# driver_2.net
KiCad netlist of a schematic drawn in EAGLE
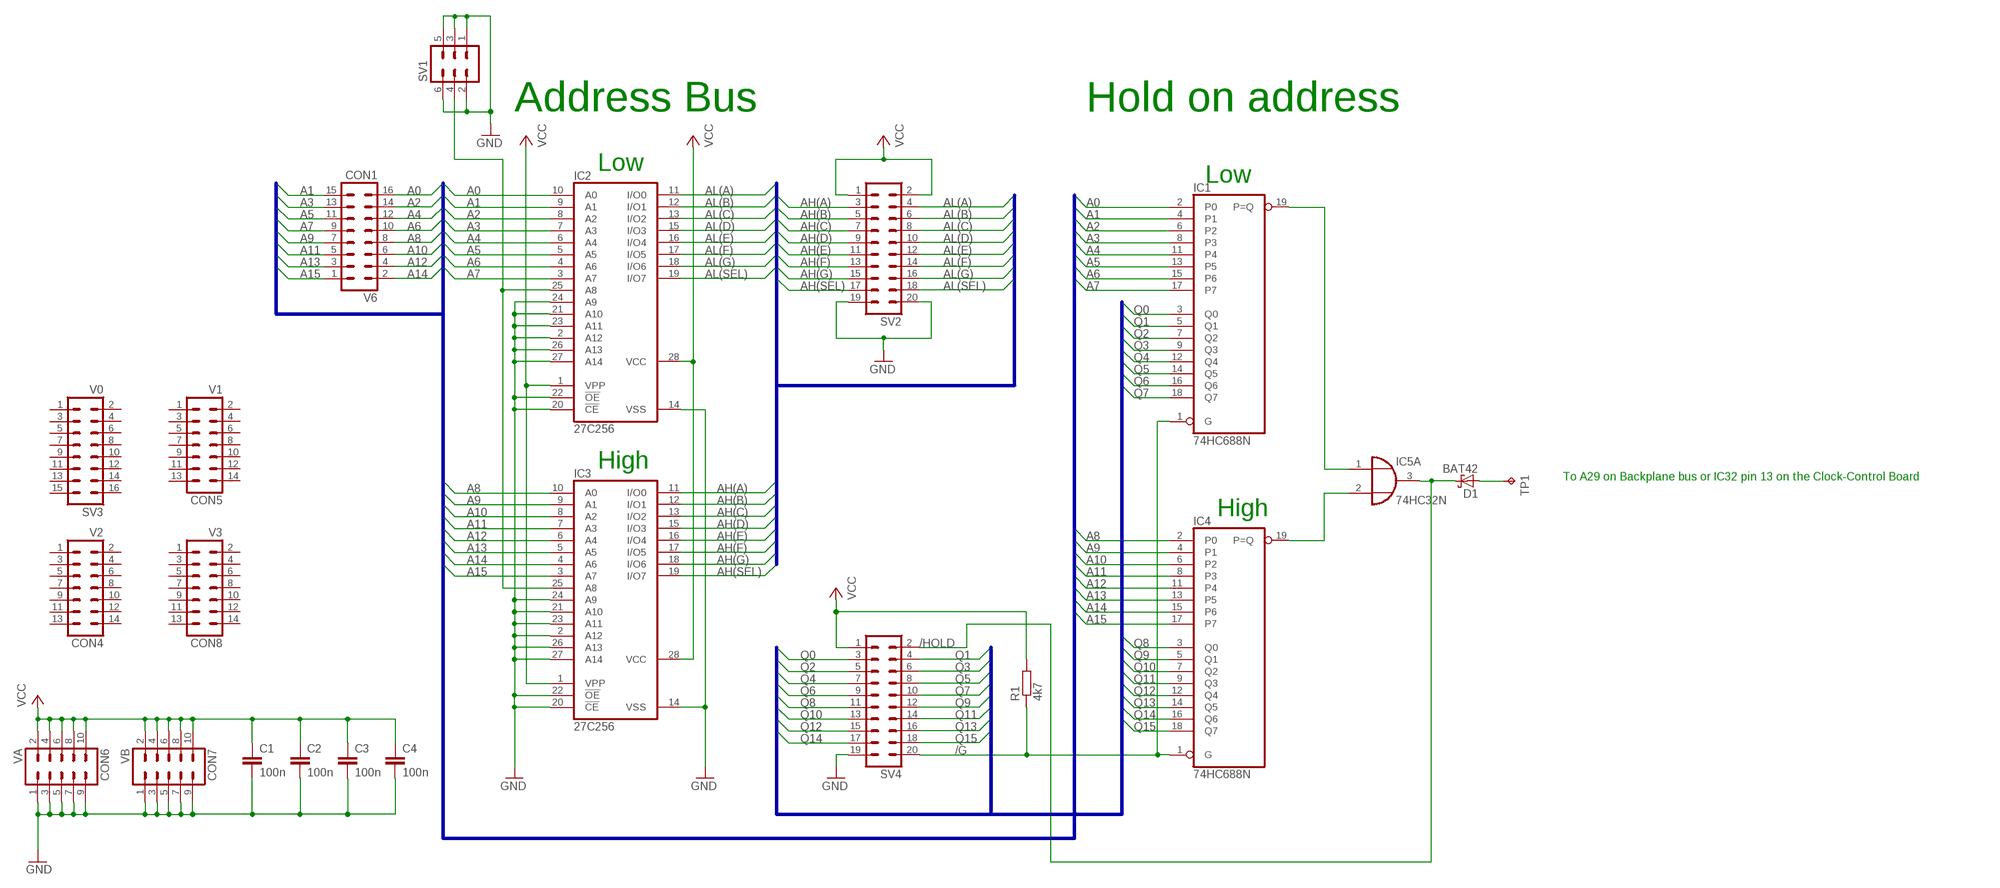
[diagram p0: schematic, sheet 1]

(export (version "E")
  (design (tool "Eeschema 10.0.6"))
  (components
    (comp (ref "C1")
      (value "100n")
      (footprint "eagle-import:C050-024X044")
      (libsource (lib "eagle-import") (part "C-EU050-024X044"))
    )
    (comp (ref "C2")
      (value "100n")
      (footprint "eagle-import:C050-024X044")
      (libsource (lib "eagle-import") (part "C-EU050-024X044"))
    )
    (comp (ref "C3")
      (value "100n")
      (footprint "eagle-import:C050-024X044")
      (libsource (lib "eagle-import") (part "C-EU050-024X044"))
    )
    (comp (ref "C4")
      (value "100n")
      (footprint "eagle-import:C050-024X044")
      (libsource (lib "eagle-import") (part "C-EU050-024X044"))
    )
    (comp (ref "CON1")
      (value "V6")
      (footprint "eagle-import:ML16")
      (libsource (lib "eagle-import") (part "ML16"))
    )
    (comp (ref "CON4")
      (value "V2")
      (footprint "eagle-import:ML14")
      (libsource (lib "eagle-import") (part "ML14"))
    )
    (comp (ref "CON5")
      (value "V1")
      (footprint "eagle-import:ML14")
      (fields (field (name "OC_FARNELL") "unknown") (field (name "OC_NEWARK") "unknown"))
      (libsource (lib "eagle-import") (part "ML14"))
    )
    (comp (ref "CON6")
      (value "VA")
      (footprint "eagle-import:ML10")
      (libsource (lib "eagle-import") (part "ML10"))
    )
    (comp (ref "CON7")
      (value "VB")
      (footprint "eagle-import:ML10")
      (libsource (lib "eagle-import") (part "ML10"))
    )
    (comp (ref "CON8")
      (value "V3")
      (footprint "eagle-import:ML14")
      (libsource (lib "eagle-import") (part "ML14"))
    )
    (comp (ref "D1")
      (value "BAT42")
      (footprint "eagle-import:DO35-10")
      (libsource (lib "eagle-import") (part "BAT42"))
    )
    (comp (ref "IC1")
      (value "74HC688N")
      (footprint "eagle-import:DIL20")
      (libsource (lib "eagle-import") (part "74688NHC"))
    )
    (comp (ref "IC2")
      (value "27C256")
      (footprint "eagle-import:DIL28-6")
      (libsource (lib "eagle-import") (part "27C256AG"))
    )
    (comp (ref "IC3")
      (value "27C256")
      (footprint "eagle-import:DIL28-6")
      (libsource (lib "eagle-import") (part "27C256AG"))
    )
    (comp (ref "IC4")
      (value "74HC688N")
      (footprint "eagle-import:DIL20")
      (libsource (lib "eagle-import") (part "74688NHC"))
    )
    (comp (ref "IC5")
      (value "74HC32N")
      (footprint "eagle-import:DIL14")
      (libsource (lib "eagle-import") (part "7432NHC"))
    )
    (comp (ref "R1")
      (value "4k7")
      (footprint "eagle-import:0204_5")
      (libsource (lib "eagle-import") (part "R-EU_0204/5"))
    )
    (comp (ref "SV1")
      (value "ML6")
      (footprint "eagle-import:ML6")
      (libsource (lib "eagle-import") (part "ML6"))
    )
    (comp (ref "SV2")
      (value "ML20L")
      (footprint "eagle-import:ML20L")
      (libsource (lib "eagle-import") (part "ML20L"))
    )
    (comp (ref "SV3")
      (value "V0")
      (footprint "eagle-import:ML16")
      (libsource (lib "eagle-import") (part "ML16"))
    )
    (comp (ref "SV4")
      (value "ML20L")
      (footprint "eagle-import:ML20L")
      (libsource (lib "eagle-import") (part "ML20L"))
    )
    (comp (ref "TP1")
      (value "Interface -> R12")
      (footprint "eagle-import:P1-17")
      (libsource (lib "eagle-import") (part "TPPAD1-17"))
    )
  )
  (nets
    (net (code "1") (name "/A0") (class "Default")
      (node (ref "CON1") (pin "16") (pinfunction "16_16") (pintype "passive"))
      (node (ref "IC1") (pin "2") (pinfunction "P0_2") (pintype "input"))
      (node (ref "IC2") (pin "10") (pinfunction "A0_10") (pintype "input"))
    )
    (net (code "2") (name "/A1") (class "Default")
      (node (ref "CON1") (pin "15") (pinfunction "15_15") (pintype "passive"))
      (node (ref "IC1") (pin "4") (pinfunction "P1_4") (pintype "input"))
      (node (ref "IC2") (pin "9") (pinfunction "A1_9") (pintype "input"))
    )
    (net (code "3") (name "/A2") (class "Default")
      (node (ref "CON1") (pin "14") (pinfunction "14_14") (pintype "passive"))
      (node (ref "IC1") (pin "6") (pinfunction "P2_6") (pintype "input"))
      (node (ref "IC2") (pin "8") (pinfunction "A2_8") (pintype "input"))
    )
    (net (code "4") (name "/A3") (class "Default")
      (node (ref "CON1") (pin "13") (pinfunction "13_13") (pintype "passive"))
      (node (ref "IC1") (pin "8") (pinfunction "P3_8") (pintype "input"))
      (node (ref "IC2") (pin "7") (pinfunction "A3_7") (pintype "input"))
    )
    (net (code "5") (name "/A4") (class "Default")
      (node (ref "CON1") (pin "12") (pinfunction "12_12") (pintype "passive"))
      (node (ref "IC1") (pin "11") (pinfunction "P4_11") (pintype "input"))
      (node (ref "IC2") (pin "6") (pinfunction "A4_6") (pintype "input"))
    )
    (net (code "6") (name "/A5") (class "Default")
      (node (ref "CON1") (pin "11") (pinfunction "11_11") (pintype "passive"))
      (node (ref "IC1") (pin "13") (pinfunction "P5_13") (pintype "input"))
      (node (ref "IC2") (pin "5") (pinfunction "A5_5") (pintype "input"))
    )
    (net (code "7") (name "/A6") (class "Default")
      (node (ref "CON1") (pin "10") (pinfunction "10_10") (pintype "passive"))
      (node (ref "IC1") (pin "15") (pinfunction "P6_15") (pintype "input"))
      (node (ref "IC2") (pin "4") (pinfunction "A6_4") (pintype "input"))
    )
    (net (code "8") (name "/A7") (class "Default")
      (node (ref "CON1") (pin "9") (pinfunction "9_9") (pintype "passive"))
      (node (ref "IC1") (pin "17") (pinfunction "P7_17") (pintype "input"))
      (node (ref "IC2") (pin "3") (pinfunction "A7_3") (pintype "input"))
    )
    (net (code "9") (name "/A8") (class "Default")
      (node (ref "CON1") (pin "8") (pinfunction "8_8") (pintype "passive"))
      (node (ref "IC3") (pin "10") (pinfunction "A0_10") (pintype "input"))
      (node (ref "IC4") (pin "2") (pinfunction "P0_2") (pintype "input"))
    )
    (net (code "10") (name "/A9") (class "Default")
      (node (ref "CON1") (pin "7") (pinfunction "7_7") (pintype "passive"))
      (node (ref "IC3") (pin "9") (pinfunction "A1_9") (pintype "input"))
      (node (ref "IC4") (pin "4") (pinfunction "P1_4") (pintype "input"))
    )
    (net (code "11") (name "/A10") (class "Default")
      (node (ref "CON1") (pin "6") (pinfunction "6_6") (pintype "passive"))
      (node (ref "IC3") (pin "8") (pinfunction "A2_8") (pintype "input"))
      (node (ref "IC4") (pin "6") (pinfunction "P2_6") (pintype "input"))
    )
    (net (code "12") (name "/A11") (class "Default")
      (node (ref "CON1") (pin "5") (pinfunction "5_5") (pintype "passive"))
      (node (ref "IC3") (pin "7") (pinfunction "A3_7") (pintype "input"))
      (node (ref "IC4") (pin "8") (pinfunction "P3_8") (pintype "input"))
    )
    (net (code "13") (name "/A12") (class "Default")
      (node (ref "CON1") (pin "4") (pinfunction "4_4") (pintype "passive"))
      (node (ref "IC3") (pin "6") (pinfunction "A4_6") (pintype "input"))
      (node (ref "IC4") (pin "11") (pinfunction "P4_11") (pintype "input"))
    )
    (net (code "14") (name "/A13") (class "Default")
      (node (ref "CON1") (pin "3") (pinfunction "3_3") (pintype "passive"))
      (node (ref "IC3") (pin "5") (pinfunction "A5_5") (pintype "input"))
      (node (ref "IC4") (pin "13") (pinfunction "P5_13") (pintype "input"))
    )
    (net (code "15") (name "/A14") (class "Default")
      (node (ref "CON1") (pin "2") (pinfunction "2_2") (pintype "passive"))
      (node (ref "IC3") (pin "4") (pinfunction "A6_4") (pintype "input"))
      (node (ref "IC4") (pin "15") (pinfunction "P6_15") (pintype "input"))
    )
    (net (code "16") (name "/A15") (class "Default")
      (node (ref "CON1") (pin "1") (pinfunction "1_1") (pintype "passive"))
      (node (ref "IC3") (pin "3") (pinfunction "A7_3") (pintype "input"))
      (node (ref "IC4") (pin "17") (pinfunction "P7_17") (pintype "input"))
    )
    (net (code "17") (name "/AH(A)") (class "Default")
      (node (ref "IC3") (pin "11") (pinfunction "I/O0_11") (pintype "tri_state"))
      (node (ref "SV2") (pin "3") (pinfunction "3_3") (pintype "passive"))
    )
    (net (code "18") (name "/AH(B)") (class "Default")
      (node (ref "IC3") (pin "12") (pinfunction "I/O1_12") (pintype "tri_state"))
      (node (ref "SV2") (pin "5") (pinfunction "5_5") (pintype "passive"))
    )
    (net (code "19") (name "/AH(C)") (class "Default")
      (node (ref "IC3") (pin "13") (pinfunction "I/O2_13") (pintype "tri_state"))
      (node (ref "SV2") (pin "7") (pinfunction "7_7") (pintype "passive"))
    )
    (net (code "20") (name "/AH(D)") (class "Default")
      (node (ref "IC3") (pin "15") (pinfunction "I/O3_15") (pintype "tri_state"))
      (node (ref "SV2") (pin "9") (pinfunction "9_9") (pintype "passive"))
    )
    (net (code "21") (name "/AH(E)") (class "Default")
      (node (ref "IC3") (pin "16") (pinfunction "I/O4_16") (pintype "tri_state"))
      (node (ref "SV2") (pin "11") (pinfunction "11_11") (pintype "passive"))
    )
    (net (code "22") (name "/AH(F)") (class "Default")
      (node (ref "IC3") (pin "17") (pinfunction "I/O5_17") (pintype "tri_state"))
      (node (ref "SV2") (pin "13") (pinfunction "13_13") (pintype "passive"))
    )
    (net (code "23") (name "/AH(G)") (class "Default")
      (node (ref "IC3") (pin "18") (pinfunction "I/O6_18") (pintype "tri_state"))
      (node (ref "SV2") (pin "15") (pinfunction "15_15") (pintype "passive"))
    )
    (net (code "24") (name "/AH(SEL)") (class "Default")
      (node (ref "IC3") (pin "19") (pinfunction "I/O7_19") (pintype "tri_state"))
      (node (ref "SV2") (pin "17") (pinfunction "17_17") (pintype "passive"))
    )
    (net (code "25") (name "/AL(A)") (class "Default")
      (node (ref "IC2") (pin "11") (pinfunction "I/O0_11") (pintype "tri_state"))
      (node (ref "SV2") (pin "4") (pinfunction "4_4") (pintype "passive"))
    )
    (net (code "26") (name "/AL(B)") (class "Default")
      (node (ref "IC2") (pin "12") (pinfunction "I/O1_12") (pintype "tri_state"))
      (node (ref "SV2") (pin "6") (pinfunction "6_6") (pintype "passive"))
    )
    (net (code "27") (name "/AL(C)") (class "Default")
      (node (ref "IC2") (pin "13") (pinfunction "I/O2_13") (pintype "tri_state"))
      (node (ref "SV2") (pin "8") (pinfunction "8_8") (pintype "passive"))
    )
    (net (code "28") (name "/AL(D)") (class "Default")
      (node (ref "IC2") (pin "15") (pinfunction "I/O3_15") (pintype "tri_state"))
      (node (ref "SV2") (pin "10") (pinfunction "10_10") (pintype "passive"))
    )
    (net (code "29") (name "/AL(E)") (class "Default")
      (node (ref "IC2") (pin "16") (pinfunction "I/O4_16") (pintype "tri_state"))
      (node (ref "SV2") (pin "12") (pinfunction "12_12") (pintype "passive"))
    )
    (net (code "30") (name "/AL(F)") (class "Default")
      (node (ref "IC2") (pin "17") (pinfunction "I/O5_17") (pintype "tri_state"))
      (node (ref "SV2") (pin "14") (pinfunction "14_14") (pintype "passive"))
    )
    (net (code "31") (name "/AL(G)") (class "Default")
      (node (ref "IC2") (pin "18") (pinfunction "I/O6_18") (pintype "tri_state"))
      (node (ref "SV2") (pin "16") (pinfunction "16_16") (pintype "passive"))
    )
    (net (code "32") (name "/AL(SEL)") (class "Default")
      (node (ref "IC2") (pin "19") (pinfunction "I/O7_19") (pintype "tri_state"))
      (node (ref "SV2") (pin "18") (pinfunction "18_18") (pintype "passive"))
    )
    (net (code "33") (name "/Q0") (class "Default")
      (node (ref "IC1") (pin "3") (pinfunction "Q0_3") (pintype "input"))
      (node (ref "SV4") (pin "3") (pinfunction "3_3") (pintype "passive"))
    )
    (net (code "34") (name "/Q1") (class "Default")
      (node (ref "IC1") (pin "5") (pinfunction "Q1_5") (pintype "input"))
      (node (ref "SV4") (pin "4") (pinfunction "4_4") (pintype "passive"))
    )
    (net (code "35") (name "/Q2") (class "Default")
      (node (ref "IC1") (pin "7") (pinfunction "Q2_7") (pintype "input"))
      (node (ref "SV4") (pin "5") (pinfunction "5_5") (pintype "passive"))
    )
    (net (code "36") (name "/Q3") (class "Default")
      (node (ref "IC1") (pin "9") (pinfunction "Q3_9") (pintype "input"))
      (node (ref "SV4") (pin "6") (pinfunction "6_6") (pintype "passive"))
    )
    (net (code "37") (name "/Q4") (class "Default")
      (node (ref "IC1") (pin "12") (pinfunction "Q4_12") (pintype "input"))
      (node (ref "SV4") (pin "7") (pinfunction "7_7") (pintype "passive"))
    )
    (net (code "38") (name "/Q5") (class "Default")
      (node (ref "IC1") (pin "14") (pinfunction "Q5_14") (pintype "input"))
      (node (ref "SV4") (pin "8") (pinfunction "8_8") (pintype "passive"))
    )
    (net (code "39") (name "/Q6") (class "Default")
      (node (ref "IC1") (pin "16") (pinfunction "Q6_16") (pintype "input"))
      (node (ref "SV4") (pin "9") (pinfunction "9_9") (pintype "passive"))
    )
    (net (code "40") (name "/Q7") (class "Default")
      (node (ref "IC1") (pin "18") (pinfunction "Q7_18") (pintype "input"))
      (node (ref "SV4") (pin "10") (pinfunction "10_10") (pintype "passive"))
    )
    (net (code "41") (name "/Q8") (class "Default")
      (node (ref "IC4") (pin "3") (pinfunction "Q0_3") (pintype "input"))
      (node (ref "SV4") (pin "11") (pinfunction "11_11") (pintype "passive"))
    )
    (net (code "42") (name "/Q9") (class "Default")
      (node (ref "IC4") (pin "5") (pinfunction "Q1_5") (pintype "input"))
      (node (ref "SV4") (pin "12") (pinfunction "12_12") (pintype "passive"))
    )
    (net (code "43") (name "/Q10") (class "Default")
      (node (ref "IC4") (pin "7") (pinfunction "Q2_7") (pintype "input"))
      (node (ref "SV4") (pin "13") (pinfunction "13_13") (pintype "passive"))
    )
    (net (code "44") (name "/Q11") (class "Default")
      (node (ref "IC4") (pin "9") (pinfunction "Q3_9") (pintype "input"))
      (node (ref "SV4") (pin "14") (pinfunction "14_14") (pintype "passive"))
    )
    (net (code "45") (name "/Q12") (class "Default")
      (node (ref "IC4") (pin "12") (pinfunction "Q4_12") (pintype "input"))
      (node (ref "SV4") (pin "15") (pinfunction "15_15") (pintype "passive"))
    )
    (net (code "46") (name "/Q13") (class "Default")
      (node (ref "IC4") (pin "14") (pinfunction "Q5_14") (pintype "input"))
      (node (ref "SV4") (pin "16") (pinfunction "16_16") (pintype "passive"))
    )
    (net (code "47") (name "/Q14") (class "Default")
      (node (ref "IC4") (pin "16") (pinfunction "Q6_16") (pintype "input"))
      (node (ref "SV4") (pin "17") (pinfunction "17_17") (pintype "passive"))
    )
    (net (code "48") (name "/Q15") (class "Default")
      (node (ref "IC4") (pin "18") (pinfunction "Q7_18") (pintype "input"))
      (node (ref "SV4") (pin "18") (pinfunction "18_18") (pintype "passive"))
    )
    (net (code "49") (name "/{slash}G") (class "Default")
      (node (ref "IC1") (pin "1") (pinfunction "G_1") (pintype "input"))
      (node (ref "IC4") (pin "1") (pinfunction "G_1") (pintype "input"))
      (node (ref "R1") (pin "1") (pinfunction "1_1") (pintype "passive"))
      (node (ref "SV4") (pin "20") (pinfunction "20_20") (pintype "passive"))
    )
    (net (code "50") (name "/{slash}HOLD") (class "Default")
      (node (ref "D1") (pin "C") (pinfunction "C_C") (pintype "passive"))
      (node (ref "IC5") (pin "3") (pinfunction "O_3") (pintype "output"))
      (node (ref "SV4") (pin "2") (pinfunction "2_2") (pintype "passive"))
    )
    (net (code "51") (name "GND") (class "Default")
      (node (ref "C1") (pin "2") (pinfunction "2_2") (pintype "passive"))
      (node (ref "C2") (pin "2") (pinfunction "2_2") (pintype "passive"))
      (node (ref "C3") (pin "2") (pinfunction "2_2") (pintype "passive"))
      (node (ref "C4") (pin "2") (pinfunction "2_2") (pintype "passive"))
      (node (ref "CON6") (pin "1") (pinfunction "1_1") (pintype "passive"))
      (node (ref "CON6") (pin "3") (pinfunction "3_3") (pintype "passive"))
      (node (ref "CON6") (pin "5") (pinfunction "5_5") (pintype "passive"))
      (node (ref "CON6") (pin "7") (pinfunction "7_7") (pintype "passive"))
      (node (ref "CON6") (pin "9") (pinfunction "9_9") (pintype "passive"))
      (node (ref "CON7") (pin "1") (pinfunction "1_1") (pintype "passive"))
      (node (ref "CON7") (pin "3") (pinfunction "3_3") (pintype "passive"))
      (node (ref "CON7") (pin "5") (pinfunction "5_5") (pintype "passive"))
      (node (ref "CON7") (pin "7") (pinfunction "7_7") (pintype "passive"))
      (node (ref "CON7") (pin "9") (pinfunction "9_9") (pintype "passive"))
      (node (ref "IC2") (pin "14") (pinfunction "VSS_14") (pintype "power_in"))
      (node (ref "IC2") (pin "2") (pinfunction "A12_2") (pintype "input"))
      (node (ref "IC2") (pin "20") (pinfunction "~{CE}_20") (pintype "input"))
      (node (ref "IC2") (pin "21") (pinfunction "A10_21") (pintype "input"))
      (node (ref "IC2") (pin "22") (pinfunction "~{OE}_22") (pintype "input"))
      (node (ref "IC2") (pin "23") (pinfunction "A11_23") (pintype "input"))
      (node (ref "IC2") (pin "24") (pinfunction "A9_24") (pintype "input"))
      (node (ref "IC2") (pin "26") (pinfunction "A13_26") (pintype "input"))
      (node (ref "IC2") (pin "27") (pinfunction "A14_27") (pintype "input"))
      (node (ref "IC3") (pin "14") (pinfunction "VSS_14") (pintype "power_in"))
      (node (ref "IC3") (pin "2") (pinfunction "A12_2") (pintype "input"))
      (node (ref "IC3") (pin "20") (pinfunction "~{CE}_20") (pintype "input"))
      (node (ref "IC3") (pin "21") (pinfunction "A10_21") (pintype "input"))
      (node (ref "IC3") (pin "22") (pinfunction "~{OE}_22") (pintype "input"))
      (node (ref "IC3") (pin "23") (pinfunction "A11_23") (pintype "input"))
      (node (ref "IC3") (pin "24") (pinfunction "A9_24") (pintype "input"))
      (node (ref "IC3") (pin "26") (pinfunction "A13_26") (pintype "input"))
      (node (ref "IC3") (pin "27") (pinfunction "A14_27") (pintype "input"))
      (node (ref "SV1") (pin "1") (pinfunction "1_1") (pintype "passive"))
      (node (ref "SV1") (pin "2") (pinfunction "2_2") (pintype "passive"))
      (node (ref "SV1") (pin "3") (pinfunction "3_3") (pintype "passive"))
      (node (ref "SV1") (pin "5") (pinfunction "5_5") (pintype "passive"))
      (node (ref "SV1") (pin "6") (pinfunction "6_6") (pintype "passive"))
      (node (ref "SV2") (pin "19") (pinfunction "19_19") (pintype "passive"))
      (node (ref "SV2") (pin "20") (pinfunction "20_20") (pintype "passive"))
      (node (ref "SV4") (pin "19") (pinfunction "19_19") (pintype "passive"))
    )
    (net (code "52") (name "Net-(D1-PadA)") (class "Default")
      (node (ref "D1") (pin "A") (pinfunction "A_A") (pintype "passive"))
      (node (ref "TP1") (pin "TP") (pinfunction "TP_TP") (pintype "input"))
    )
    (net (code "53") (name "Net-(IC1A-P=Q)") (class "Default")
      (node (ref "IC1") (pin "19") (pinfunction "P=Q_19") (pintype "output"))
      (node (ref "IC5") (pin "1") (pinfunction "I0_1") (pintype "input"))
    )
    (net (code "54") (name "Net-(IC2-A8)") (class "Default")
      (node (ref "IC2") (pin "25") (pinfunction "A8_25") (pintype "input"))
      (node (ref "IC3") (pin "25") (pinfunction "A8_25") (pintype "input"))
      (node (ref "SV1") (pin "4") (pinfunction "4_4") (pintype "passive"))
    )
    (net (code "55") (name "Net-(IC4A-P=Q)") (class "Default")
      (node (ref "IC4") (pin "19") (pinfunction "P=Q_19") (pintype "output"))
      (node (ref "IC5") (pin "2") (pinfunction "I1_2") (pintype "input"))
    )
    (net (code "56") (name "VCC") (class "Default")
      (node (ref "C1") (pin "1") (pinfunction "1_1") (pintype "passive"))
      (node (ref "C2") (pin "1") (pinfunction "1_1") (pintype "passive"))
      (node (ref "C3") (pin "1") (pinfunction "1_1") (pintype "passive"))
      (node (ref "C4") (pin "1") (pinfunction "1_1") (pintype "passive"))
      (node (ref "CON6") (pin "10") (pinfunction "10_10") (pintype "passive"))
      (node (ref "CON6") (pin "2") (pinfunction "2_2") (pintype "passive"))
      (node (ref "CON6") (pin "4") (pinfunction "4_4") (pintype "passive"))
      (node (ref "CON6") (pin "6") (pinfunction "6_6") (pintype "passive"))
      (node (ref "CON6") (pin "8") (pinfunction "8_8") (pintype "passive"))
      (node (ref "CON7") (pin "10") (pinfunction "10_10") (pintype "passive"))
      (node (ref "CON7") (pin "2") (pinfunction "2_2") (pintype "passive"))
      (node (ref "CON7") (pin "4") (pinfunction "4_4") (pintype "passive"))
      (node (ref "CON7") (pin "6") (pinfunction "6_6") (pintype "passive"))
      (node (ref "CON7") (pin "8") (pinfunction "8_8") (pintype "passive"))
      (node (ref "IC2") (pin "1") (pinfunction "VPP_1") (pintype "input"))
      (node (ref "IC2") (pin "28") (pinfunction "VCC_28") (pintype "power_in"))
      (node (ref "IC3") (pin "1") (pinfunction "VPP_1") (pintype "input"))
      (node (ref "IC3") (pin "28") (pinfunction "VCC_28") (pintype "power_in"))
      (node (ref "R1") (pin "2") (pinfunction "2_2") (pintype "passive"))
      (node (ref "SV2") (pin "1") (pinfunction "1_1") (pintype "passive"))
      (node (ref "SV2") (pin "2") (pinfunction "2_2") (pintype "passive"))
      (node (ref "SV4") (pin "1") (pinfunction "1_1") (pintype "passive"))
    )
    (net (code "57") (name "unconnected-(CON4-Pad1)") (class "Default")
      (node (ref "CON4") (pin "1") (pinfunction "1_1") (pintype "passive"))
    )
    (net (code "58") (name "unconnected-(CON4-Pad2)") (class "Default")
      (node (ref "CON4") (pin "2") (pinfunction "2_2") (pintype "passive"))
    )
    (net (code "59") (name "unconnected-(CON4-Pad3)") (class "Default")
      (node (ref "CON4") (pin "3") (pinfunction "3_3") (pintype "passive"))
    )
    (net (code "60") (name "unconnected-(CON4-Pad4)") (class "Default")
      (node (ref "CON4") (pin "4") (pinfunction "4_4") (pintype "passive"))
    )
    (net (code "61") (name "unconnected-(CON4-Pad5)") (class "Default")
      (node (ref "CON4") (pin "5") (pinfunction "5_5") (pintype "passive"))
    )
    (net (code "62") (name "unconnected-(CON4-Pad6)") (class "Default")
      (node (ref "CON4") (pin "6") (pinfunction "6_6") (pintype "passive"))
    )
    (net (code "63") (name "unconnected-(CON4-Pad7)") (class "Default")
      (node (ref "CON4") (pin "7") (pinfunction "7_7") (pintype "passive"))
    )
    (net (code "64") (name "unconnected-(CON4-Pad8)") (class "Default")
      (node (ref "CON4") (pin "8") (pinfunction "8_8") (pintype "passive"))
    )
    (net (code "65") (name "unconnected-(CON4-Pad9)") (class "Default")
      (node (ref "CON4") (pin "9") (pinfunction "9_9") (pintype "passive"))
    )
    (net (code "66") (name "unconnected-(CON4-Pad10)") (class "Default")
      (node (ref "CON4") (pin "10") (pinfunction "10_10") (pintype "passive"))
    )
    (net (code "67") (name "unconnected-(CON4-Pad11)") (class "Default")
      (node (ref "CON4") (pin "11") (pinfunction "11_11") (pintype "passive"))
    )
    (net (code "68") (name "unconnected-(CON4-Pad12)") (class "Default")
      (node (ref "CON4") (pin "12") (pinfunction "12_12") (pintype "passive"))
    )
    (net (code "69") (name "unconnected-(CON4-Pad13)") (class "Default")
      (node (ref "CON4") (pin "13") (pinfunction "13_13") (pintype "passive"))
    )
    (net (code "70") (name "unconnected-(CON4-Pad14)") (class "Default")
      (node (ref "CON4") (pin "14") (pinfunction "14_14") (pintype "passive"))
    )
    (net (code "71") (name "unconnected-(CON5-Pad1)") (class "Default")
      (node (ref "CON5") (pin "1") (pinfunction "1_1") (pintype "passive"))
    )
    (net (code "72") (name "unconnected-(CON5-Pad2)") (class "Default")
      (node (ref "CON5") (pin "2") (pinfunction "2_2") (pintype "passive"))
    )
    (net (code "73") (name "unconnected-(CON5-Pad3)") (class "Default")
      (node (ref "CON5") (pin "3") (pinfunction "3_3") (pintype "passive"))
    )
    (net (code "74") (name "unconnected-(CON5-Pad4)") (class "Default")
      (node (ref "CON5") (pin "4") (pinfunction "4_4") (pintype "passive"))
    )
    (net (code "75") (name "unconnected-(CON5-Pad5)") (class "Default")
      (node (ref "CON5") (pin "5") (pinfunction "5_5") (pintype "passive"))
    )
    (net (code "76") (name "unconnected-(CON5-Pad6)") (class "Default")
      (node (ref "CON5") (pin "6") (pinfunction "6_6") (pintype "passive"))
    )
    (net (code "77") (name "unconnected-(CON5-Pad7)") (class "Default")
      (node (ref "CON5") (pin "7") (pinfunction "7_7") (pintype "passive"))
    )
    (net (code "78") (name "unconnected-(CON5-Pad8)") (class "Default")
      (node (ref "CON5") (pin "8") (pinfunction "8_8") (pintype "passive"))
    )
    (net (code "79") (name "unconnected-(CON5-Pad9)") (class "Default")
      (node (ref "CON5") (pin "9") (pinfunction "9_9") (pintype "passive"))
    )
    (net (code "80") (name "unconnected-(CON5-Pad10)") (class "Default")
      (node (ref "CON5") (pin "10") (pinfunction "10_10") (pintype "passive"))
    )
    (net (code "81") (name "unconnected-(CON5-Pad11)") (class "Default")
      (node (ref "CON5") (pin "11") (pinfunction "11_11") (pintype "passive"))
    )
    (net (code "82") (name "unconnected-(CON5-Pad12)") (class "Default")
      (node (ref "CON5") (pin "12") (pinfunction "12_12") (pintype "passive"))
    )
    (net (code "83") (name "unconnected-(CON5-Pad13)") (class "Default")
      (node (ref "CON5") (pin "13") (pinfunction "13_13") (pintype "passive"))
    )
    (net (code "84") (name "unconnected-(CON5-Pad14)") (class "Default")
      (node (ref "CON5") (pin "14") (pinfunction "14_14") (pintype "passive"))
    )
    (net (code "85") (name "unconnected-(CON8-Pad1)") (class "Default")
      (node (ref "CON8") (pin "1") (pinfunction "1_1") (pintype "passive"))
    )
    (net (code "86") (name "unconnected-(CON8-Pad2)") (class "Default")
      (node (ref "CON8") (pin "2") (pinfunction "2_2") (pintype "passive"))
    )
    (net (code "87") (name "unconnected-(CON8-Pad3)") (class "Default")
      (node (ref "CON8") (pin "3") (pinfunction "3_3") (pintype "passive"))
    )
    (net (code "88") (name "unconnected-(CON8-Pad4)") (class "Default")
      (node (ref "CON8") (pin "4") (pinfunction "4_4") (pintype "passive"))
    )
    (net (code "89") (name "unconnected-(CON8-Pad5)") (class "Default")
      (node (ref "CON8") (pin "5") (pinfunction "5_5") (pintype "passive"))
    )
    (net (code "90") (name "unconnected-(CON8-Pad6)") (class "Default")
      (node (ref "CON8") (pin "6") (pinfunction "6_6") (pintype "passive"))
    )
    (net (code "91") (name "unconnected-(CON8-Pad7)") (class "Default")
      (node (ref "CON8") (pin "7") (pinfunction "7_7") (pintype "passive"))
    )
    (net (code "92") (name "unconnected-(CON8-Pad8)") (class "Default")
      (node (ref "CON8") (pin "8") (pinfunction "8_8") (pintype "passive"))
    )
    (net (code "93") (name "unconnected-(CON8-Pad9)") (class "Default")
      (node (ref "CON8") (pin "9") (pinfunction "9_9") (pintype "passive"))
    )
    (net (code "94") (name "unconnected-(CON8-Pad10)") (class "Default")
      (node (ref "CON8") (pin "10") (pinfunction "10_10") (pintype "passive"))
    )
    (net (code "95") (name "unconnected-(CON8-Pad11)") (class "Default")
      (node (ref "CON8") (pin "11") (pinfunction "11_11") (pintype "passive"))
    )
    (net (code "96") (name "unconnected-(CON8-Pad12)") (class "Default")
      (node (ref "CON8") (pin "12") (pinfunction "12_12") (pintype "passive"))
    )
    (net (code "97") (name "unconnected-(CON8-Pad13)") (class "Default")
      (node (ref "CON8") (pin "13") (pinfunction "13_13") (pintype "passive"))
    )
    (net (code "98") (name "unconnected-(CON8-Pad14)") (class "Default")
      (node (ref "CON8") (pin "14") (pinfunction "14_14") (pintype "passive"))
    )
    (net (code "99") (name "unconnected-(SV3-Pad1)") (class "Default")
      (node (ref "SV3") (pin "1") (pinfunction "1_1") (pintype "passive"))
    )
    (net (code "100") (name "unconnected-(SV3-Pad2)") (class "Default")
      (node (ref "SV3") (pin "2") (pinfunction "2_2") (pintype "passive"))
    )
    (net (code "101") (name "unconnected-(SV3-Pad3)") (class "Default")
      (node (ref "SV3") (pin "3") (pinfunction "3_3") (pintype "passive"))
    )
    (net (code "102") (name "unconnected-(SV3-Pad4)") (class "Default")
      (node (ref "SV3") (pin "4") (pinfunction "4_4") (pintype "passive"))
    )
    (net (code "103") (name "unconnected-(SV3-Pad5)") (class "Default")
      (node (ref "SV3") (pin "5") (pinfunction "5_5") (pintype "passive"))
    )
    (net (code "104") (name "unconnected-(SV3-Pad6)") (class "Default")
      (node (ref "SV3") (pin "6") (pinfunction "6_6") (pintype "passive"))
    )
    (net (code "105") (name "unconnected-(SV3-Pad7)") (class "Default")
      (node (ref "SV3") (pin "7") (pinfunction "7_7") (pintype "passive"))
    )
    (net (code "106") (name "unconnected-(SV3-Pad8)") (class "Default")
      (node (ref "SV3") (pin "8") (pinfunction "8_8") (pintype "passive"))
    )
    (net (code "107") (name "unconnected-(SV3-Pad9)") (class "Default")
      (node (ref "SV3") (pin "9") (pinfunction "9_9") (pintype "passive"))
    )
    (net (code "108") (name "unconnected-(SV3-Pad10)") (class "Default")
      (node (ref "SV3") (pin "10") (pinfunction "10_10") (pintype "passive"))
    )
    (net (code "109") (name "unconnected-(SV3-Pad11)") (class "Default")
      (node (ref "SV3") (pin "11") (pinfunction "11_11") (pintype "passive"))
    )
    (net (code "110") (name "unconnected-(SV3-Pad12)") (class "Default")
      (node (ref "SV3") (pin "12") (pinfunction "12_12") (pintype "passive"))
    )
    (net (code "111") (name "unconnected-(SV3-Pad13)") (class "Default")
      (node (ref "SV3") (pin "13") (pinfunction "13_13") (pintype "passive"))
    )
    (net (code "112") (name "unconnected-(SV3-Pad14)") (class "Default")
      (node (ref "SV3") (pin "14") (pinfunction "14_14") (pintype "passive"))
    )
    (net (code "113") (name "unconnected-(SV3-Pad15)") (class "Default")
      (node (ref "SV3") (pin "15") (pinfunction "15_15") (pintype "passive"))
    )
    (net (code "114") (name "unconnected-(SV3-Pad16)") (class "Default")
      (node (ref "SV3") (pin "16") (pinfunction "16_16") (pintype "passive"))
    )
  )
)
